# ProDoc_hapTGP_2025-10-23.net
KiCad netlist of a schematic drawn in EasyEDA Pro
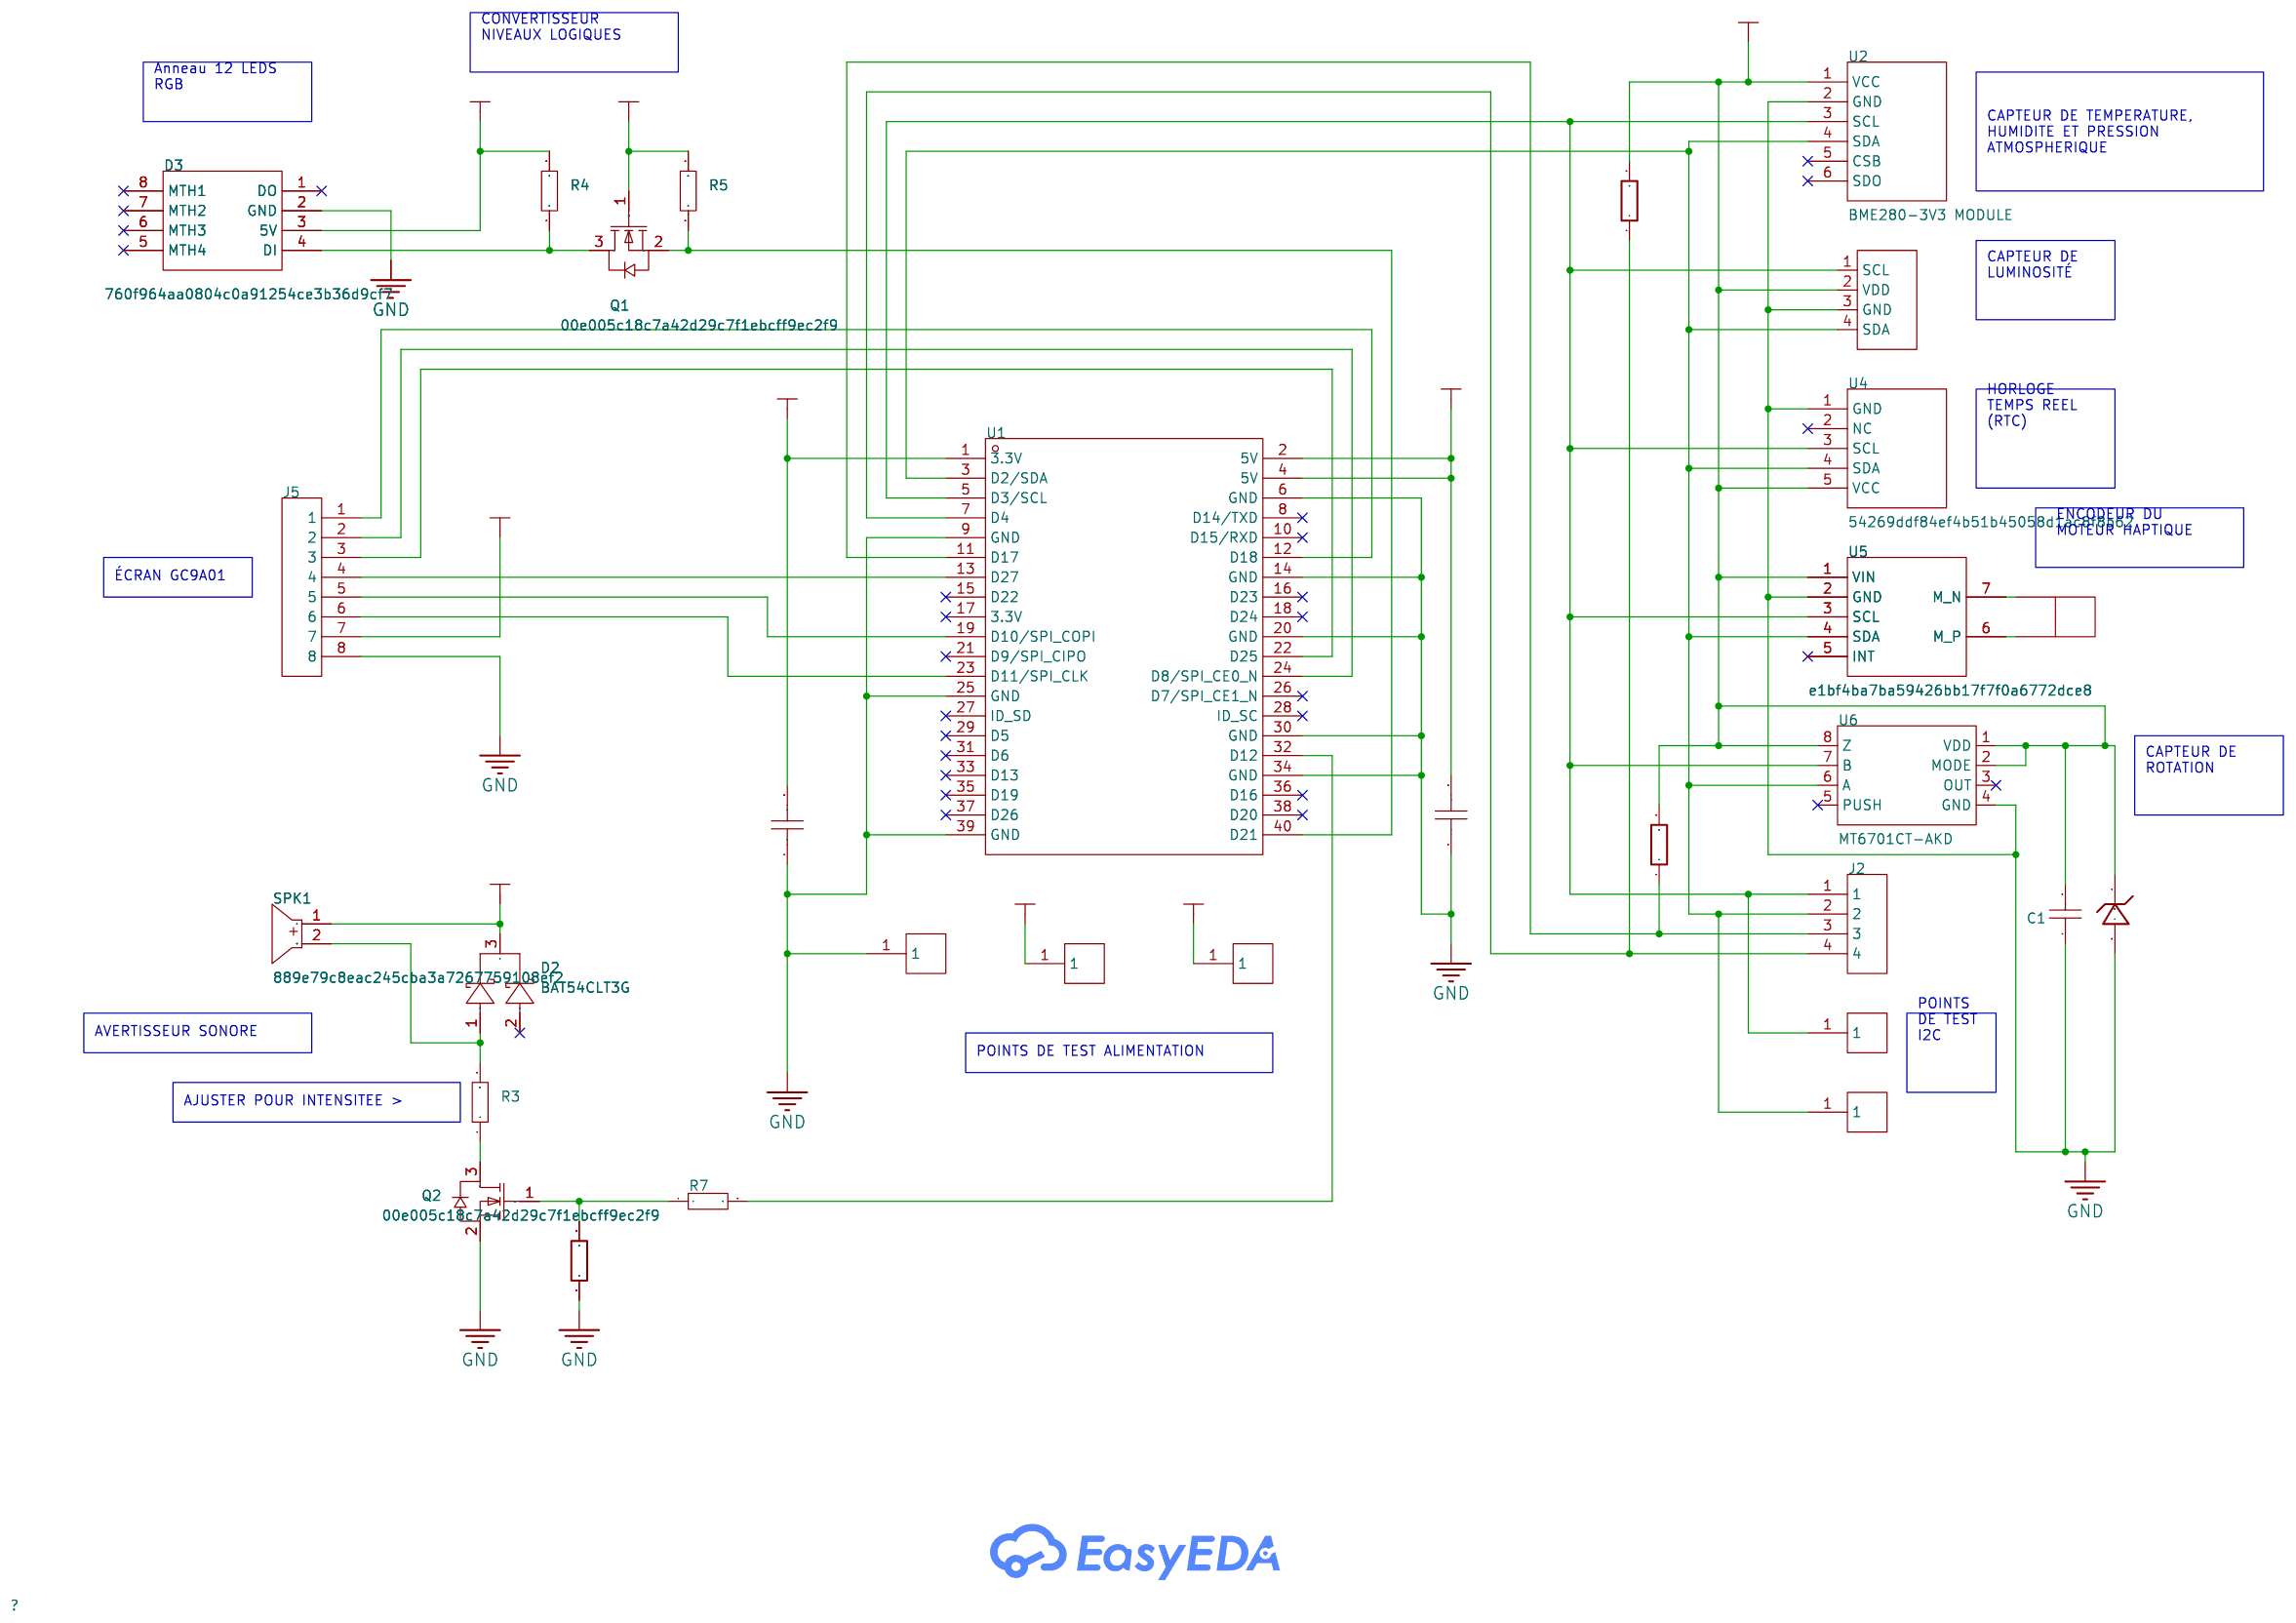
[diagram p0: P1]
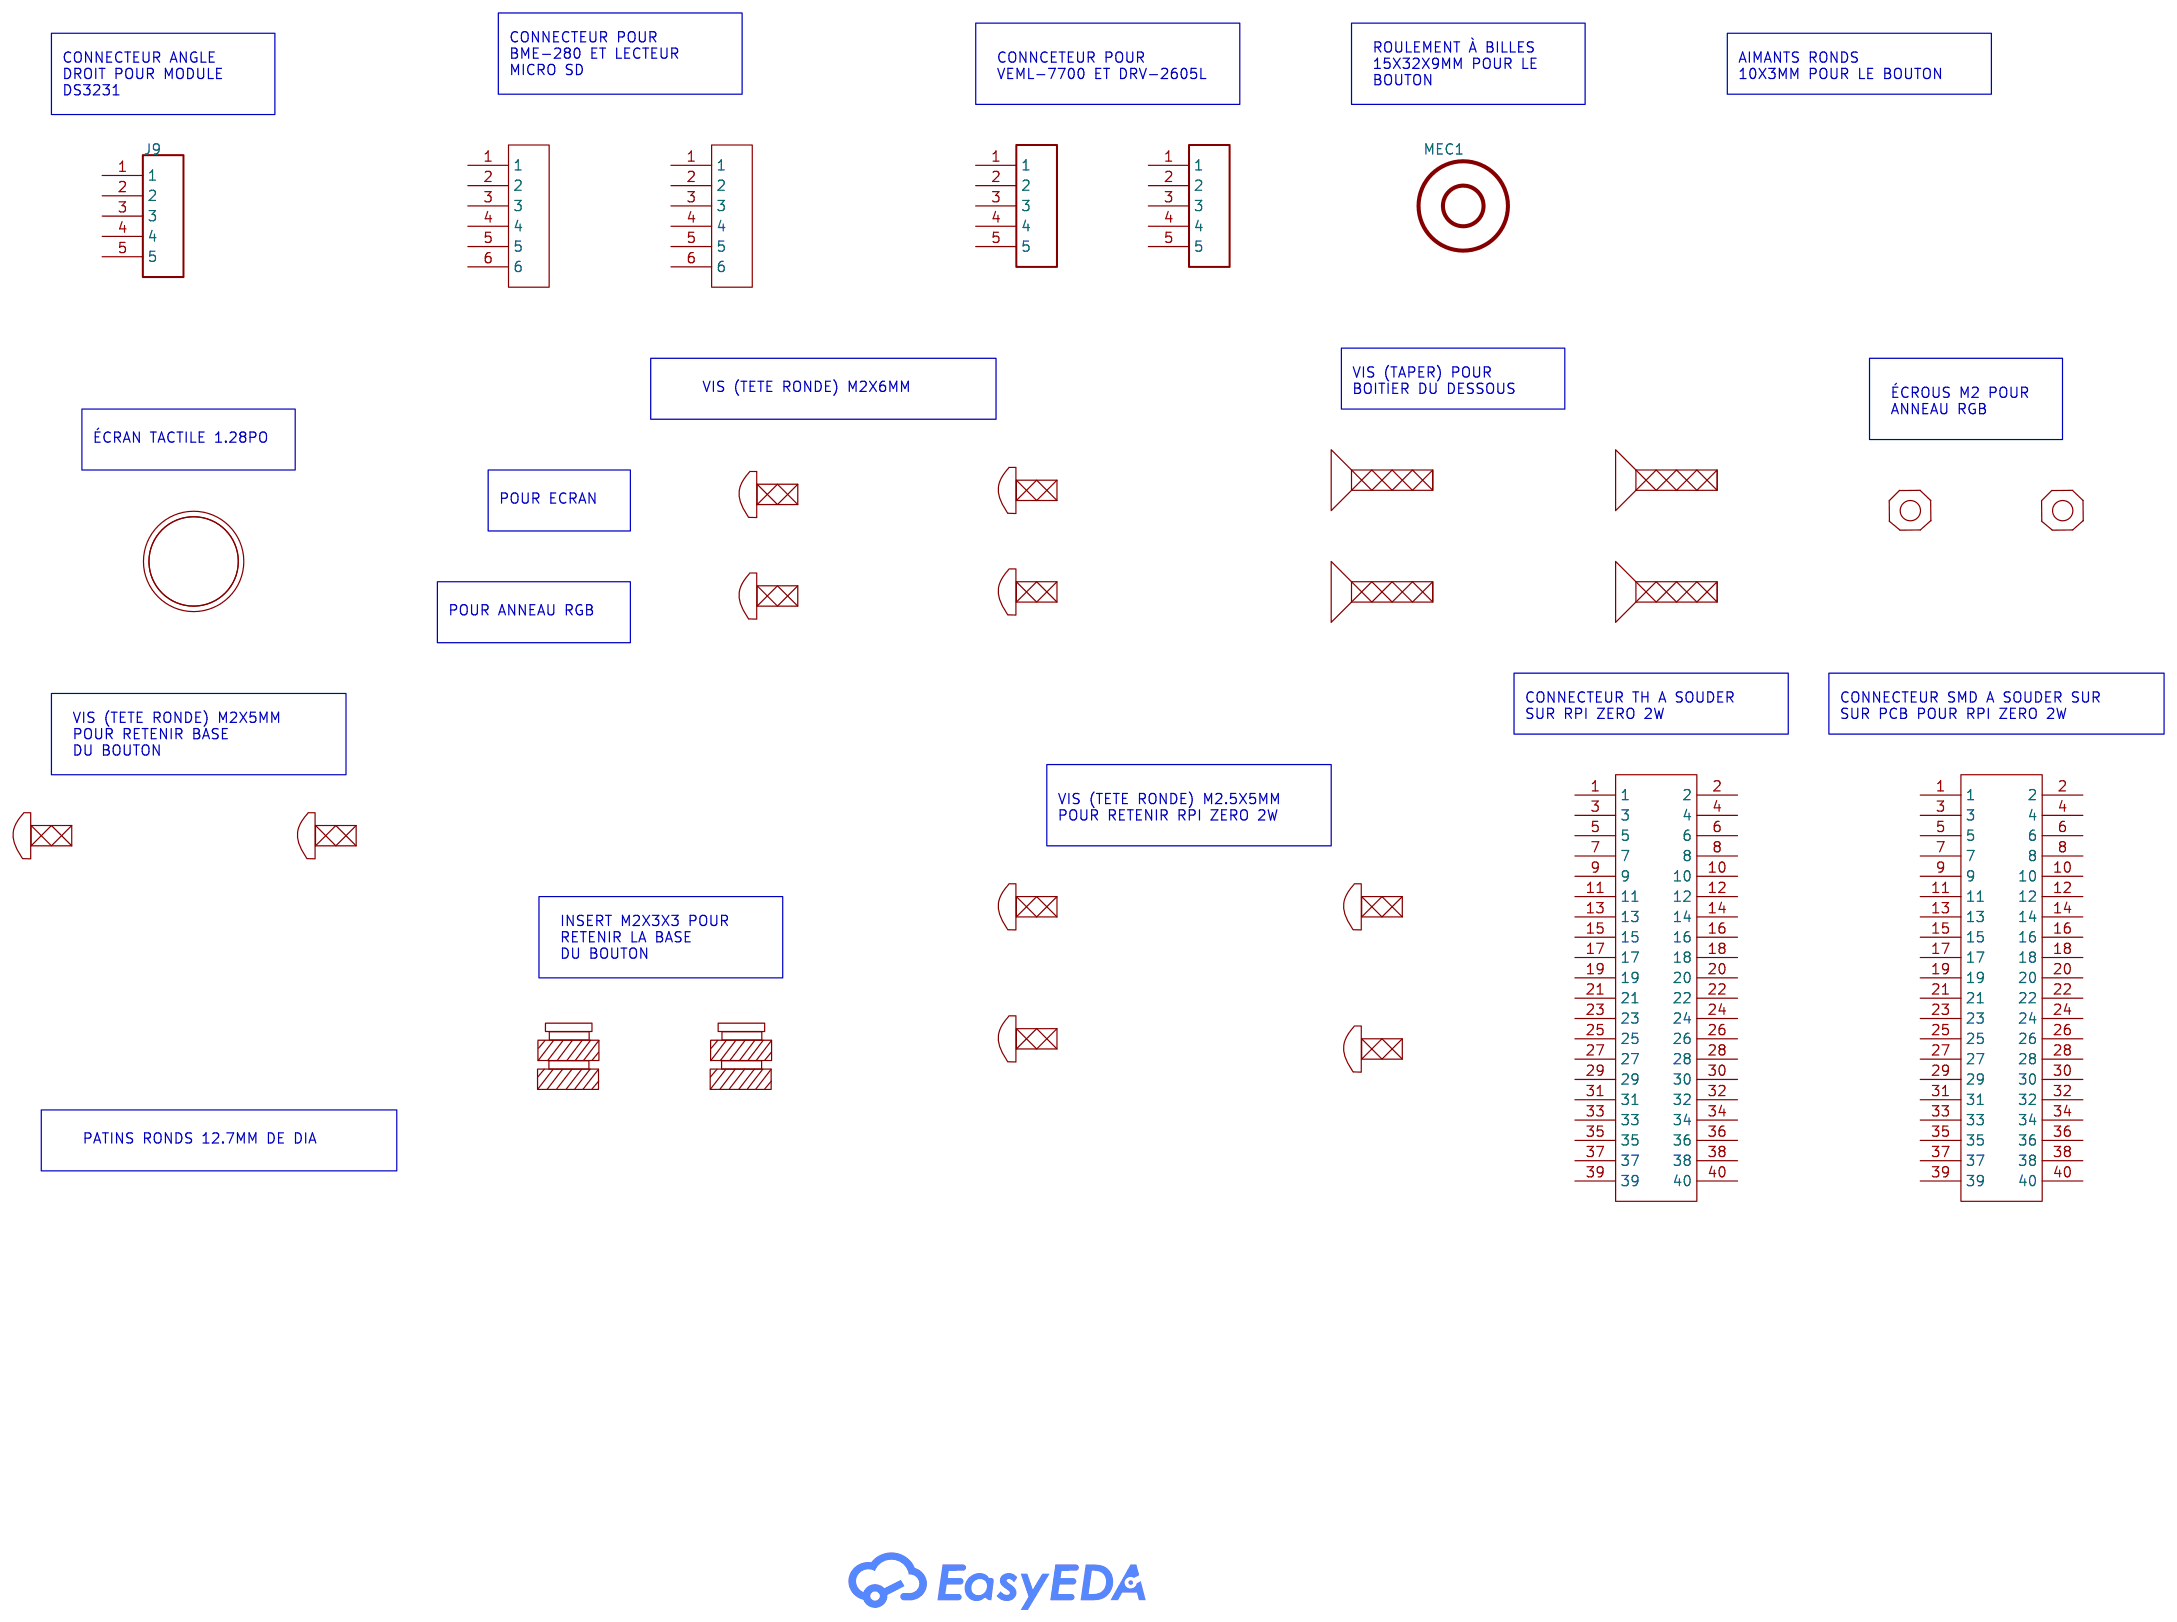
[diagram p1: P2]

(export (version "E")
  (design (tool "Eeschema 10.0.6"))
  (components
    (comp (ref "C1")
      (value "0.1uF")
      (footprint "easyedapro:C1206")
      (description "0.1 µF ±20% 50V Ceramic Capacitor X7R 1206 (3216 Metric)")
      (fields (field (name "Manufacturer Part") "C1206C104M5RAC7800") (field (name "Manufacturer") "KEMET"))
      (libsource (lib "easyedapro") (part "C1206C104M5RAC7800"))
    )
    (comp (ref "C2")
      (value "10µF")
      (footprint "easyedapro:C1206")
      (description "10 µF ±20% 16V Ceramic Capacitor X7R 1206 (3216 Metric)")
      (fields
        (field (name "Manufacturer Part") "CL31B106MOHNNNE")
        (field (name "Manufacturer") "Samsung Electro-Mechanics")
      )
      (libsource (lib "easyedapro") (part "CL31B106MOHNNNE"))
    )
    (comp (ref "C3")
      (value "10µF")
      (footprint "easyedapro:C1206")
      (description "10 µF ±20% 16V Ceramic Capacitor X7R 1206 (3216 Metric)")
      (fields
        (field (name "Manufacturer Part") "CL31B106MOHNNNE")
        (field (name "Manufacturer") "Samsung Electro-Mechanics")
      )
      (libsource (lib "easyedapro") (part "CL31B106MOHNNNE"))
    )
    (comp (ref "D1")
      (value "786c42ee781a49819dcb2175513ac30d")
      (footprint "easyedapro:SMA_L4.3-W2.6-LS5.2-RD")
      (description "10.3V Clamp 38.8A Ipp Tvs Diode Surface Mount DO-214AC (SMA)")
      (fields (field (name "Manufacturer Part") "SMAJ6.0A") (field (name "Manufacturer") "Littelfuse Inc."))
      (libsource (lib "easyedapro") (part "SMAJ6.0A"))
    )
    (comp (ref "D2")
      (value "BAT54CLT3G")
      (footprint "easyedapro:SOT-23-3_L2.9-W1.3-P1.90-LS2.4-BR_LONG_PAD")
      (description "Diode Array 1 Pair Common Cathode 30 V 200mA (DC) Surface Mount TO-236-3, SC-59, SOT-23-3")
      (fields (field (name "Manufacturer") "onsemi"))
      (libsource (lib "easyedapro") (part "BAT54C/SOT23"))
    )
    (comp (ref "D3")
      (value "760f964aa0804c0a91254ce3b36d9cf7")
      (footprint "easyedapro:12BIT_WS2812_RING")
      (description "12 Bit WS2812 Neopixel Ring")
      (fields
        (field (name "Manufacturer Part") "Color: 12 Bit")
        (field (name "Manufacturer") "WAVGAT Official Store")
      )
      (libsource (lib "easyedapro") (part "12BIT_WS2812_RING"))
    )
    (comp (ref "J2")
      (value "df3f6e4d750841a1978b57070b38a967")
      (footprint "easyedapro:TSW-104-07-G-S")
      (description "Connector Header Through Hole 4 position 0.100\" (2.54mm)")
      (fields (field (name "Manufacturer Part") "TSW-104-07-G-S") (field (name "Manufacturer") "Samtec"))
      (libsource (lib "easyedapro") (part "TSW-104-07-G-S"))
    )
    (comp (ref "J3")
      (value "25d9ce5fcc824b51a382671083746301")
      (footprint "easyedapro:TSW-101-07-G-S")
      (description "Connector Header Through Hole 1 position")
      (fields (field (name "Manufacturer Part") "TSW-101-07-G-S") (field (name "Manufacturer") "Samtec"))
      (libsource (lib "easyedapro") (part "TSW-101-07-G-S"))
    )
    (comp (ref "J4")
      (value "25d9ce5fcc824b51a382671083746301")
      (footprint "easyedapro:TSW-101-07-G-S")
      (description "Connector Header Through Hole 1 position")
      (fields (field (name "Manufacturer Part") "TSW-101-07-G-S") (field (name "Manufacturer") "Samtec"))
      (libsource (lib "easyedapro") (part "TSW-101-07-G-S"))
    )
    (comp (ref "J5")
      (value "db50c67101b641f09feebbd75da13b19")
      (footprint "easyedapro:TSW-108-07-G-S")
      (description "Connector Header Through Hole 8 position 0.100\" (2.54mm)")
      (fields (field (name "Manufacturer Part") "TSW-108-07-G-S") (field (name "Manufacturer") "Samtec"))
      (libsource (lib "easyedapro") (part "TSW-108-07-G-S"))
    )
    (comp (ref "J6")
      (value "25d9ce5fcc824b51a382671083746301")
      (footprint "easyedapro:TSW-101-07-G-S")
      (description "Connector Header Through Hole 1 position")
      (fields (field (name "Manufacturer Part") "TSW-101-07-G-S") (field (name "Manufacturer") "Samtec"))
      (libsource (lib "easyedapro") (part "TSW-101-07-G-S"))
    )
    (comp (ref "J7")
      (value "25d9ce5fcc824b51a382671083746301")
      (footprint "easyedapro:TSW-101-07-G-S")
      (description "Connector Header Through Hole 1 position")
      (fields (field (name "Manufacturer Part") "TSW-101-07-G-S") (field (name "Manufacturer") "Samtec"))
      (libsource (lib "easyedapro") (part "TSW-101-07-G-S"))
    )
    (comp (ref "J8")
      (value "25d9ce5fcc824b51a382671083746301")
      (footprint "easyedapro:TSW-101-07-G-S")
      (description "Connector Header Through Hole 1 position")
      (fields (field (name "Manufacturer Part") "TSW-101-07-G-S") (field (name "Manufacturer") "Samtec"))
      (libsource (lib "easyedapro") (part "TSW-101-07-G-S"))
    )
    (comp (ref "M1")
      (value "a87b66f22e6449f7bc229c794d7d3cd7")
      (description "DC Motor Vibration, ERM (Haptic) 3VDC")
      (fields
        (field (name "Manufacturer Part") "316040001")
        (field (name "Manufacturer") "Seeed Technology Co., Ltd")
      )
      (libsource (lib "easyedapro") (part "HAPTIC_MOTOR_10X2MM"))
    )
    (comp (ref "Q1")
      (value "00e005c18c7a42d29c7f1ebcff9ec2f9")
      (footprint "easyedapro:SOT-23-3_L2.9-W1.3-P1.90-LS2.4-BR_LONG_PAD")
      (description "N-Channel 50 V 170mA 350mW (Ta) Surface Mount SOT-23-3")
      (fields (field (name "Manufacturer Part") "BSS138") (field (name "Manufacturer") "OnSemi"))
      (libsource (lib "easyedapro") (part "BSS138"))
    )
    (comp (ref "Q2")
      (value "00e005c18c7a42d29c7f1ebcff9ec2f9")
      (footprint "easyedapro:SOT-23-3_L2.9-W1.3-P1.90-LS2.4-BR_LONG_PAD")
      (description "N-Channel 50 V 170mA 350mW (Ta) Surface Mount SOT-23-3")
      (fields (field (name "Manufacturer Part") "BSS138") (field (name "Manufacturer") "OnSemi"))
      (libsource (lib "easyedapro") (part "BSS138"))
    )
    (comp (ref "R1")
      (value "10kΩ")
      (footprint "easyedapro:R1206")
      (description "10 kOhms ±1% 0.25W, 1/4W Chip Resistor 1206 (3216 Metric) Automotive AEC-Q200 Thick Film")
      (fields
        (field (name "Manufacturer Part") "RMCF1206FT10K0")
        (field (name "Manufacturer") "Stackpole Electronics Inc")
      )
      (libsource (lib "easyedapro") (part "RMCF1206FT10K0"))
    )
    (comp (ref "R3")
      (value "100Ω")
      (footprint "easyedapro:R1206")
      (description "100 Ohms ±1% 0.25W, 1/4W Chip Resistor 1206 (3216 Metric) Automotive AEC-Q200 Thick Film")
      (fields
        (field (name "Manufacturer Part") "RMCF1206FG100R")
        (field (name "Manufacturer") "Stackpole Electronics Inc")
      )
      (libsource (lib "easyedapro") (part "RMCF1206FG100R"))
    )
    (comp (ref "R4")
      (value "1kΩ")
      (footprint "easyedapro:R1206")
      (description "1 kOhms ±1% 0.5W, 1/2W Chip Resistor 1206 (3216 Metric) Anti-Sulfur Thin Film")
      (fields
        (field (name "Manufacturer Part") "RNCP1206FTD1K00")
        (field (name "Manufacturer") "Stackpole Electronics Inc")
      )
      (libsource (lib "easyedapro") (part "RNCP1206FTD1K00"))
    )
    (comp (ref "R5")
      (value "1kΩ")
      (footprint "easyedapro:R1206")
      (description "1 kOhms ±1% 0.5W, 1/2W Chip Resistor 1206 (3216 Metric) Anti-Sulfur Thin Film")
      (fields
        (field (name "Manufacturer Part") "RNCP1206FTD1K00")
        (field (name "Manufacturer") "Stackpole Electronics Inc")
      )
      (libsource (lib "easyedapro") (part "RNCP1206FTD1K00"))
    )
    (comp (ref "R6")
      (value "10kΩ")
      (footprint "easyedapro:R1206")
      (description "10 kOhms ±1% 0.25W, 1/4W Chip Resistor 1206 (3216 Metric) Automotive AEC-Q200 Thick Film")
      (fields
        (field (name "Manufacturer Part") "RMCF1206FT10K0")
        (field (name "Manufacturer") "Stackpole Electronics Inc")
      )
      (libsource (lib "easyedapro") (part "RMCF1206FT10K0"))
    )
    (comp (ref "R7")
      (value "22.1Ω")
      (footprint "easyedapro:R1206")
      (description "22.1 Ohms ±1% 0.5W, 1/2W Chip Resistor 1206 (3216 Metric) Anti-Sulfur Thin Film")
      (fields
        (field (name "Manufacturer Part") "RNCP1206FTD22R1")
        (field (name "Manufacturer") "Stackpole Electronics Inc")
      )
      (libsource (lib "easyedapro") (part "RNCP1206FTD22R1"))
    )
    (comp (ref "R8")
      (value "3.32kΩ")
      (footprint "easyedapro:R1206")
      (description "3.32 kOhms ±1% 0.25W, 1/4W Chip Resistor 1206 (3216 Metric) Automotive AEC-Q200 Thick Film")
      (fields
        (field (name "Manufacturer Part") "RMCF1206FT3K32")
        (field (name "Manufacturer") "Stackpole Electronics Inc")
      )
      (libsource (lib "easyedapro") (part "RMCF1206FT3K32"))
    )
    (comp (ref "SPK1")
      (value "2.048kHz")
      (footprint "easyedapro:CEM-1203(42)")
      (fields (field (name "Manufacturer Part") "CEM-1203(42)") (field (name "Manufacturer") "CUI"))
      (libsource (lib "easyedapro") (part "CEM-1203(42)"))
    )
    (comp (ref "U1")
      (value "82908ec7757f43da87b5bf82fbb97953")
      (footprint "easyedapro:RPI_ZERO_2W_SMD")
      (fields (field (name "Manufacturer Part") "SC1176") (field (name "Manufacturer") "Raspberry Pi"))
      (libsource (lib "easyedapro") (part "RPI_ZERO_2W_SMD"))
    )
    (comp (ref "U2")
      (value "BME280-3V3 MODULE")
      (footprint "easyedapro:BME280-3V3")
      (description "Humidity, Pressure, Temperature 0 ~ 100% RH I2C, SPI ±3% 1 s Surface Mount")
      (fields
        (field (name "Manufacturer Part") "GY-BME280-3.3V")
        (field (name "Manufacturer") "Simple Robot Store")
      )
      (libsource (lib "easyedapro") (part "BME280-3V3 MODULE"))
    )
    (comp (ref "U4")
      (value "54269ddf84ef4b51b45058d1ac8f8b62")
      (footprint "easyedapro:DS3231_FOR_PI")
      (description "Real Time Clock (RTC) IC Clock/Calendar I2C, 2-Wire Serial")
      (fields (field (name "Manufacturer Part") "DS3231") (field (name "Manufacturer") "Simple Robot Store"))
      (libsource (lib "easyedapro") (part "DS3231_FOR_PI"))
    )
    (comp (ref "U5")
      (value "e1bf4ba7ba59426bb17f7f0a6772dce8")
      (footprint "easyedapro:DRV2605L_MODULE")
      (description "Adafruit DRV2605L Haptic Motor Controller")
      (fields
        (field (name "Manufacturer Part") "Color: Driving module")
        (field (name "Manufacturer") "Simple Robot Store")
      )
      (libsource (lib "easyedapro") (part "DRV2605L_MODULE"))
    )
    (comp (ref "U6")
      (value "MT6701CT-AKD")
      (footprint "easyedapro:SOIC-8_MT6701_LONG_PAD")
      (description "Hall Based Angle Position Encoder Sensor")
      (fields
        (field (name "Manufacturer Part") "SOP8-IIC Default")
        (field (name "Manufacturer") "Red Yellow Store")
      )
      (libsource (lib "easyedapro") (part "MT6701CT-AKD"))
    )
    (comp (ref "U7")
      (value "e600161ae6e94e2281b32d82396dab58")
      (footprint "easyedapro:VEML7700-TT")
      (description "Optical Sensor Ambient I2C 4-SMD, J-Lead - Top View")
      (fields (field (name "Manufacturer Part") "VEML7700-TT") (field (name "Manufacturer") "Vishay"))
      (libsource (lib "easyedapro") (part "VEML7700-TT"))
    )
    (comp (ref "J9")
      (value "d4bc78de218c43d6890ff5c2e1751f38")
      (footprint "easyedapro:TSW-105-08-G-S-RA")
      (description "Connector Header Through Hole, Right Angle 5 position 0.100\" (2.54mm)")
      (fields (field (name "Manufacturer Part") "TSW-105-08-G-S-RA") (field (name "Manufacturer") "Samtec"))
      (libsource (lib "easyedapro") (part "TSW-105-08-G-S-RA"))
    )
    (comp (ref "J10")
      (value "842bb1afb25c4c82b2ce2c1a00fc9b49")
      (footprint "easyedapro:TSW-106-07-G-S")
      (description "Connector Header Through Hole 6 position 0.100\" (2.54mm)")
      (fields (field (name "Manufacturer Part") "TSW-106-07-G-S") (field (name "Manufacturer") "Samtec"))
      (libsource (lib "easyedapro") (part "TSW-106-07-G-S"))
    )
    (comp (ref "J11")
      (value "842bb1afb25c4c82b2ce2c1a00fc9b49")
      (footprint "easyedapro:TSW-106-07-G-S")
      (description "Connector Header Through Hole 6 position 0.100\" (2.54mm)")
      (fields (field (name "Manufacturer Part") "TSW-106-07-G-S") (field (name "Manufacturer") "Samtec"))
      (libsource (lib "easyedapro") (part "TSW-106-07-G-S"))
    )
    (comp (ref "J12")
      (value "519a3672ea174b5fbedaf20516a41a10")
      (footprint "easyedapro:TSW-105-07-G-S")
      (description "Connector Header Through Hole 5 position 0.100\" (2.54mm)")
      (fields (field (name "Manufacturer Part") "TSW-105-07-G-S") (field (name "Manufacturer") "Samtec"))
      (libsource (lib "easyedapro") (part "TSW-105-07-G-S"))
    )
    (comp (ref "J13")
      (value "519a3672ea174b5fbedaf20516a41a10")
      (footprint "easyedapro:TSW-105-07-G-S")
      (description "Connector Header Through Hole 5 position 0.100\" (2.54mm)")
      (fields (field (name "Manufacturer Part") "TSW-105-07-G-S") (field (name "Manufacturer") "Samtec"))
      (libsource (lib "easyedapro") (part "TSW-105-07-G-S"))
    )
    (comp (ref "J14")
      (value "320c196bd822489ebe2c8557b4e2ea87")
      (footprint "easyedapro:TSW-120-07-G-D")
      (description "Connector Header Through Hole 40 position 0.100\" (2.54mm)")
      (fields (field (name "Manufacturer Part") "TSW-120-07-G-D") (field (name "Manufacturer") "Samtec"))
      (libsource (lib "easyedapro") (part "TSW-120-07-G-D"))
    )
    (comp (ref "J15")
      (value "60a980731c99412ab857ed917eeb6bae")
      (footprint "easyedapro:SSM-120-L-DV")
      (description "40 Position Receptacle, Pass Through Connector 0.100\" (2.54mm) Surface Mount Gold")
      (fields (field (name "Manufacturer Part") "SSM-120-L-DV") (field (name "Manufacturer") "Samtec"))
      (libsource (lib "easyedapro") (part "SSM-120-L-DV"))
    )
    (comp (ref "MEC1")
      (value "4874c76d77fe4fedaef2837b43ac3319")
      (fields
        (field (name "Manufacturer Part") "6002-2RS")
        (field (name "Manufacturer") "Bearing World Store")
      )
      (libsource (lib "easyedapro") (part "BEARING_15x32x9MM"))
    )
    (comp (ref "MEC2")
      (value "a5e0b033ab874c949acdb6fa7986dbbc")
      (fields
        (field (name "Manufacturer Part") "Color: 10x3mm-10PCS")
        (field (name "Manufacturer") "Magical Magnet Life Store")
      )
      (libsource (lib "easyedapro") (part "MAGNET_10X3MM_ROUND"))
    )
    (comp (ref "MEC3")
      (value "a5e0b033ab874c949acdb6fa7986dbbc")
      (fields
        (field (name "Manufacturer Part") "Color: 10x3mm-10PCS")
        (field (name "Manufacturer") "Magical Magnet Life Store")
      )
      (libsource (lib "easyedapro") (part "MAGNET_10X3MM_ROUND"))
    )
    (comp (ref "MEC4")
      (value "55b254a44b8a4a90b11fe05f35b53fb9")
      (description "1.28 inch TFT Screen Display Module 1.28\" IPS Round Colorful LCD Board GC9A01 Touch 240x240 SPI")
      (fields
        (field (name "Manufacturer Part") "Color: Module With Touch")
        (field (name "Manufacturer") "Your Cee")
      )
      (libsource (lib "easyedapro") (part "1.28IN_TFT_TOUCH_SCREEN"))
    )
    (comp (ref "MEC5")
      (value "84bc130494194e13a6b8797a8c02c4b9")
      (description "M2 Stainless steel iron plating round head, Phillips screw bolt length 6mm")
      (fields
        (field (name "Manufacturer Part") "Size: M2, Length: 6mm")
        (field (name "Manufacturer") "Darzoom Store")
      )
      (libsource (lib "easyedapro") (part "M2x6_ROUND_HEAD_SCREW"))
    )
    (comp (ref "MEC6")
      (value "84bc130494194e13a6b8797a8c02c4b9")
      (description "M2 Stainless steel iron plating round head, Phillips screw bolt length 6mm")
      (fields
        (field (name "Manufacturer Part") "Size: M2, Length: 6mm")
        (field (name "Manufacturer") "Darzoom Store")
      )
      (libsource (lib "easyedapro") (part "M2x6_ROUND_HEAD_SCREW"))
    )
    (comp (ref "MEC7")
      (value "84bc130494194e13a6b8797a8c02c4b9")
      (description "M2 Stainless steel iron plating round head, Phillips screw bolt length 6mm")
      (fields
        (field (name "Manufacturer Part") "Size: M2, Length: 6mm")
        (field (name "Manufacturer") "Darzoom Store")
      )
      (libsource (lib "easyedapro") (part "M2x6_ROUND_HEAD_SCREW"))
    )
    (comp (ref "MEC8")
      (value "84bc130494194e13a6b8797a8c02c4b9")
      (description "M2 Stainless steel iron plating round head, Phillips screw bolt length 6mm")
      (fields
        (field (name "Manufacturer Part") "Size: M2, Length: 6mm")
        (field (name "Manufacturer") "Darzoom Store")
      )
      (libsource (lib "easyedapro") (part "M2x6_ROUND_HEAD_SCREW"))
    )
    (comp (ref "MEC9")
      (value "e747b9e705f54f58a9aa79ca04ba0c74")
      (description "M3x20mm Flat Head Machine Screws")
      (fields (field (name "Manufacturer Part") "M3x20mm") (field (name "Manufacturer") "UXCELL"))
      (libsource (lib "easyedapro") (part "M3x20_FLAT_HEAD_SCREW"))
    )
    (comp (ref "MEC10")
      (value "e747b9e705f54f58a9aa79ca04ba0c74")
      (description "M3x20mm Flat Head Machine Screws")
      (fields (field (name "Manufacturer Part") "M3x20mm") (field (name "Manufacturer") "UXCELL"))
      (libsource (lib "easyedapro") (part "M3x20_FLAT_HEAD_SCREW"))
    )
    (comp (ref "MEC11")
      (value "e747b9e705f54f58a9aa79ca04ba0c74")
      (description "M3x20mm Flat Head Machine Screws")
      (fields (field (name "Manufacturer Part") "M3x20mm") (field (name "Manufacturer") "UXCELL"))
      (libsource (lib "easyedapro") (part "M3x20_FLAT_HEAD_SCREW"))
    )
    (comp (ref "MEC12")
      (value "e747b9e705f54f58a9aa79ca04ba0c74")
      (description "M3x20mm Flat Head Machine Screws")
      (fields (field (name "Manufacturer Part") "M3x20mm") (field (name "Manufacturer") "UXCELL"))
      (libsource (lib "easyedapro") (part "M3x20_FLAT_HEAD_SCREW"))
    )
    (comp (ref "MEC13")
      (value "0744fd2aaf9640809141f7db8254e100")
      (description "M2 Stainless steel iron plating round head, Phillips screw bolt length 5mm")
      (fields
        (field (name "Manufacturer Part") "Size: M2, Length: 5mm")
        (field (name "Manufacturer") "Darzoom Store")
      )
      (libsource (lib "easyedapro") (part "M2x5_ROUND_HEAD_SCREW"))
    )
    (comp (ref "MEC14")
      (value "0744fd2aaf9640809141f7db8254e100")
      (description "M2 Stainless steel iron plating round head, Phillips screw bolt length 5mm")
      (fields
        (field (name "Manufacturer Part") "Size: M2, Length: 5mm")
        (field (name "Manufacturer") "Darzoom Store")
      )
      (libsource (lib "easyedapro") (part "M2x5_ROUND_HEAD_SCREW"))
    )
    (comp (ref "MEC15")
      (value "44b7d81d582e44f3a2eef445dd88f108")
      (description "M2.5 Stainless steel iron plating round head, Phillips screw bolt length 5mm")
      (fields
        (field (name "Manufacturer Part") "Size: M2.5, Length: 5mm")
        (field (name "Manufacturer") "Darzoom Store")
      )
      (libsource (lib "easyedapro") (part "M2.5x5_ROUND_HEAD_SCREW"))
    )
    (comp (ref "MEC16")
      (value "44b7d81d582e44f3a2eef445dd88f108")
      (description "M2.5 Stainless steel iron plating round head, Phillips screw bolt length 5mm")
      (fields
        (field (name "Manufacturer Part") "Size: M2.5, Length: 5mm")
        (field (name "Manufacturer") "Darzoom Store")
      )
      (libsource (lib "easyedapro") (part "M2.5x5_ROUND_HEAD_SCREW"))
    )
    (comp (ref "MEC17")
      (value "44b7d81d582e44f3a2eef445dd88f108")
      (description "M2.5 Stainless steel iron plating round head, Phillips screw bolt length 5mm")
      (fields
        (field (name "Manufacturer Part") "Size: M2.5, Length: 5mm")
        (field (name "Manufacturer") "Darzoom Store")
      )
      (libsource (lib "easyedapro") (part "M2.5x5_ROUND_HEAD_SCREW"))
    )
    (comp (ref "MEC18")
      (value "44b7d81d582e44f3a2eef445dd88f108")
      (description "M2.5 Stainless steel iron plating round head, Phillips screw bolt length 5mm")
      (fields
        (field (name "Manufacturer Part") "Size: M2.5, Length: 5mm")
        (field (name "Manufacturer") "Darzoom Store")
      )
      (libsource (lib "easyedapro") (part "M2.5x5_ROUND_HEAD_SCREW"))
    )
    (comp (ref "MEC19")
      (value "fea318fc1c2846968e82746a332974ab")
      (description "Stainless steel iron Hex Hexagon Nut for M2 Srew Bolt")
      (fields
        (field (name "Manufacturer Part") "Size: M2 ( 50 pcs)")
        (field (name "Manufacturer") "Darzoom Store")
      )
      (libsource (lib "easyedapro") (part "M2_HEX_NUT"))
    )
    (comp (ref "MEC20")
      (value "fea318fc1c2846968e82746a332974ab")
      (description "Stainless steel iron Hex Hexagon Nut for M2 Srew Bolt")
      (fields
        (field (name "Manufacturer Part") "Size: M2 ( 50 pcs)")
        (field (name "Manufacturer") "Darzoom Store")
      )
      (libsource (lib "easyedapro") (part "M2_HEX_NUT"))
    )
    (comp (ref "MEC21")
      (value "b4d0d6735a904df985b20de909715984")
      (description "M2 Heat Set Insert for 3D Printing Components and Plastic Parts - Brass Metric Knurled Nuts")
      (fields
        (field (name "Manufacturer Part") "Colour Name: M2 X D3 X L3(100pcs)")
        (field (name "Manufacturer") "Hanglife")
      )
      (libsource (lib "easyedapro") (part "INSERT_M2X3X3"))
    )
    (comp (ref "MEC22")
      (value "b4d0d6735a904df985b20de909715984")
      (description "M2 Heat Set Insert for 3D Printing Components and Plastic Parts - Brass Metric Knurled Nuts")
      (fields
        (field (name "Manufacturer Part") "Colour Name: M2 X D3 X L3(100pcs)")
        (field (name "Manufacturer") "Hanglife")
      )
      (libsource (lib "easyedapro") (part "INSERT_M2X3X3"))
    )
    (comp (ref "MEC23")
      (value "3b06449f621e43b7b0359324f8e45c47")
      (description "Round 12.7mm Cabinet Bumpers Soft Self-Adhesive Clear Rubber Bumper")
      (fields
        (field (name "Manufacturer Part") "Size: Cylindrical 96pcs")
        (field (name "Manufacturer") "Furnigear")
      )
      (libsource (lib "easyedapro") (part "ClearRubberBumper_12.7MM"))
    )
    (comp (ref "MEC24")
      (value "3b06449f621e43b7b0359324f8e45c47")
      (description "Round 12.7mm Cabinet Bumpers Soft Self-Adhesive Clear Rubber Bumper")
      (fields
        (field (name "Manufacturer Part") "Size: Cylindrical 96pcs")
        (field (name "Manufacturer") "Furnigear")
      )
      (libsource (lib "easyedapro") (part "ClearRubberBumper_12.7MM"))
    )
    (comp (ref "MEC25")
      (value "3b06449f621e43b7b0359324f8e45c47")
      (description "Round 12.7mm Cabinet Bumpers Soft Self-Adhesive Clear Rubber Bumper")
      (fields
        (field (name "Manufacturer Part") "Size: Cylindrical 96pcs")
        (field (name "Manufacturer") "Furnigear")
      )
      (libsource (lib "easyedapro") (part "ClearRubberBumper_12.7MM"))
    )
    (comp (ref "MEC26")
      (value "3b06449f621e43b7b0359324f8e45c47")
      (description "Round 12.7mm Cabinet Bumpers Soft Self-Adhesive Clear Rubber Bumper")
      (fields
        (field (name "Manufacturer Part") "Size: Cylindrical 96pcs")
        (field (name "Manufacturer") "Furnigear")
      )
      (libsource (lib "easyedapro") (part "ClearRubberBumper_12.7MM"))
    )
  )
  (nets
    (net (code "1") (name "3V3") (class "Default")
      (node (ref "C1") (pin "2") (pinfunction "2_2") (pintype "input"))
      (node (ref "C3") (pin "2") (pinfunction "2_2") (pintype "unspecified"))
      (node (ref "D1") (pin "1") (pinfunction "C_1") (pintype "unspecified"))
      (node (ref "D2") (pin "3") (pinfunction "K_3") (pintype "unspecified"))
      (node (ref "J5") (pin "7") (pinfunction "7_7") (pintype "input"))
      (node (ref "J8") (pin "1") (pinfunction "1_1") (pintype "unspecified"))
      (node (ref "Q1") (pin "1") (pinfunction "G_1") (pintype "unspecified"))
      (node (ref "R1") (pin "2") (pinfunction "2_2") (pintype "unspecified"))
      (node (ref "R5") (pin "2") (pinfunction "2_2") (pintype "unspecified"))
      (node (ref "R8") (pin "2") (pinfunction "2_2") (pintype "unspecified"))
      (node (ref "SPK1") (pin "1") (pinfunction "1_1") (pintype "unspecified"))
      (node (ref "U1") (pin "1") (pinfunction "3.3V_1") (pintype "unspecified"))
      (node (ref "U2") (pin "1") (pinfunction "VCC_1") (pintype "unspecified"))
      (node (ref "U4") (pin "5") (pinfunction "VCC_5") (pintype "unspecified"))
      (node (ref "U5") (pin "1") (pinfunction "VIN_1") (pintype "input"))
      (node (ref "U6") (pin "1") (pinfunction "VDD_1") (pintype "unspecified"))
      (node (ref "U6") (pin "2") (pinfunction "MODE_2") (pintype "unspecified"))
      (node (ref "U6") (pin "8") (pinfunction "Z_8") (pintype "unspecified"))
      (node (ref "U7") (pin "2") (pinfunction "VDD_2") (pintype "unspecified"))
    )
    (net (code "2") (name "5V0") (class "Default")
      (node (ref "C2") (pin "2") (pinfunction "2_2") (pintype "unspecified"))
      (node (ref "D3") (pin "3") (pinfunction "5V_3") (pintype "input"))
      (node (ref "J7") (pin "1") (pinfunction "1_1") (pintype "unspecified"))
      (node (ref "R4") (pin "2") (pinfunction "2_2") (pintype "unspecified"))
      (node (ref "U1") (pin "2") (pinfunction "5V_2") (pintype "unspecified"))
      (node (ref "U1") (pin "4") (pinfunction "5V_4") (pintype "unspecified"))
    )
    (net (code "3") (name "GND") (class "Default")
      (node (ref "C1") (pin "1") (pinfunction "1_1") (pintype "input"))
      (node (ref "C2") (pin "1") (pinfunction "1_1") (pintype "unspecified"))
      (node (ref "C3") (pin "1") (pinfunction "1_1") (pintype "unspecified"))
      (node (ref "D1") (pin "2") (pinfunction "A_2") (pintype "unspecified"))
      (node (ref "D3") (pin "2") (pinfunction "GND_2") (pintype "input"))
      (node (ref "J5") (pin "8") (pinfunction "8_8") (pintype "input"))
      (node (ref "J6") (pin "1") (pinfunction "1_1") (pintype "unspecified"))
      (node (ref "Q2") (pin "2") (pinfunction "S_2") (pintype "unspecified"))
      (node (ref "R6") (pin "1") (pinfunction "1_1") (pintype "unspecified"))
      (node (ref "U1") (pin "14") (pinfunction "GND_14") (pintype "unspecified"))
      (node (ref "U1") (pin "20") (pinfunction "GND_20") (pintype "unspecified"))
      (node (ref "U1") (pin "25") (pinfunction "GND_25") (pintype "unspecified"))
      (node (ref "U1") (pin "30") (pinfunction "GND_30") (pintype "unspecified"))
      (node (ref "U1") (pin "34") (pinfunction "GND_34") (pintype "unspecified"))
      (node (ref "U1") (pin "39") (pinfunction "GND_39") (pintype "unspecified"))
      (node (ref "U1") (pin "6") (pinfunction "GND_6") (pintype "unspecified"))
      (node (ref "U1") (pin "9") (pinfunction "GND_9") (pintype "unspecified"))
      (node (ref "U2") (pin "2") (pinfunction "GND_2") (pintype "unspecified"))
      (node (ref "U4") (pin "1") (pinfunction "GND_1") (pintype "unspecified"))
      (node (ref "U5") (pin "2") (pinfunction "GND_2") (pintype "input"))
      (node (ref "U6") (pin "4") (pinfunction "GND_4") (pintype "unspecified"))
      (node (ref "U7") (pin "3") (pinfunction "GND_3") (pintype "unspecified"))
    )
    (net (code "4") (name "Net-(D2-A-Pad1)") (class "Default")
      (node (ref "D2") (pin "1") (pinfunction "A_1") (pintype "unspecified"))
      (node (ref "R3") (pin "2") (pinfunction "2_2") (pintype "unspecified"))
      (node (ref "SPK1") (pin "2") (pinfunction "2_2") (pintype "unspecified"))
    )
    (net (code "5") (name "Net-(D3-DI)") (class "Default")
      (node (ref "D3") (pin "4") (pinfunction "DI_4") (pintype "input"))
      (node (ref "Q1") (pin "3") (pinfunction "D_3") (pintype "unspecified"))
      (node (ref "R4") (pin "1") (pinfunction "1_1") (pintype "unspecified"))
    )
    (net (code "6") (name "Net-(Q1-S)") (class "Default")
      (node (ref "Q1") (pin "2") (pinfunction "S_2") (pintype "unspecified"))
      (node (ref "R5") (pin "1") (pinfunction "1_1") (pintype "unspecified"))
      (node (ref "U1") (pin "40") (pinfunction "D21_40") (pintype "unspecified"))
    )
    (net (code "7") (name "Net-(Q2-D)") (class "Default")
      (node (ref "Q2") (pin "3") (pinfunction "D_3") (pintype "unspecified"))
      (node (ref "R3") (pin "1") (pinfunction "1_1") (pintype "unspecified"))
    )
    (net (code "8") (name "Net-(Q2-G)") (class "Default")
      (node (ref "Q2") (pin "1") (pinfunction "G_1") (pintype "unspecified"))
      (node (ref "R6") (pin "2") (pinfunction "2_2") (pintype "unspecified"))
      (node (ref "R7") (pin "1") (pinfunction "1_1") (pintype "unspecified"))
    )
    (net (code "9") (name "Net-(U1-D2{slash}SDA)") (class "Default")
      (node (ref "J2") (pin "2") (pinfunction "2_2") (pintype "input"))
      (node (ref "J4") (pin "1") (pinfunction "1_1") (pintype "unspecified"))
      (node (ref "U1") (pin "3") (pinfunction "D2/SDA_3") (pintype "unspecified"))
      (node (ref "U2") (pin "4") (pinfunction "SDA_4") (pintype "unspecified"))
      (node (ref "U4") (pin "4") (pinfunction "SDA_4") (pintype "unspecified"))
      (node (ref "U5") (pin "4") (pinfunction "SDA_4") (pintype "input"))
      (node (ref "U6") (pin "6") (pinfunction "A_6") (pintype "unspecified"))
      (node (ref "U7") (pin "4") (pinfunction "SDA_4") (pintype "unspecified"))
    )
    (net (code "10") (name "Net-(U1-D3{slash}SCL)") (class "Default")
      (node (ref "J2") (pin "1") (pinfunction "1_1") (pintype "input"))
      (node (ref "J3") (pin "1") (pinfunction "1_1") (pintype "unspecified"))
      (node (ref "U1") (pin "5") (pinfunction "D3/SCL_5") (pintype "unspecified"))
      (node (ref "U2") (pin "3") (pinfunction "SCL_3") (pintype "unspecified"))
      (node (ref "U4") (pin "3") (pinfunction "SCL_3") (pintype "unspecified"))
      (node (ref "U5") (pin "3") (pinfunction "SCL_3") (pintype "input"))
      (node (ref "U6") (pin "7") (pinfunction "B_7") (pintype "unspecified"))
      (node (ref "U7") (pin "1") (pinfunction "SCL_1") (pintype "unspecified"))
    )
    (net (code "11") (name "Net-(U1-D4)") (class "Default")
      (node (ref "J2") (pin "4") (pinfunction "4_4") (pintype "input"))
      (node (ref "R1") (pin "1") (pinfunction "1_1") (pintype "unspecified"))
      (node (ref "U1") (pin "7") (pinfunction "D4_7") (pintype "unspecified"))
    )
    (net (code "12") (name "Net-(U1-D8{slash}SPI_CE0_N)") (class "Default")
      (node (ref "J5") (pin "2") (pinfunction "2_2") (pintype "input"))
      (node (ref "U1") (pin "24") (pinfunction "D8/SPI_CE0_N_24") (pintype "unspecified"))
    )
    (net (code "13") (name "Net-(U1-D10{slash}SPI_COPI)") (class "Default")
      (node (ref "J5") (pin "5") (pinfunction "5_5") (pintype "input"))
      (node (ref "U1") (pin "19") (pinfunction "D10/SPI_COPI_19") (pintype "unspecified"))
    )
    (net (code "14") (name "Net-(U1-D11{slash}SPI_CLK)") (class "Default")
      (node (ref "J5") (pin "6") (pinfunction "6_6") (pintype "input"))
      (node (ref "U1") (pin "23") (pinfunction "D11/SPI_CLK_23") (pintype "unspecified"))
    )
    (net (code "15") (name "Net-(U1-D12)") (class "Default")
      (node (ref "R7") (pin "2") (pinfunction "2_2") (pintype "unspecified"))
      (node (ref "U1") (pin "32") (pinfunction "D12_32") (pintype "unspecified"))
    )
    (net (code "16") (name "Net-(U1-D17)") (class "Default")
      (node (ref "J2") (pin "3") (pinfunction "3_3") (pintype "input"))
      (node (ref "R8") (pin "1") (pinfunction "1_1") (pintype "unspecified"))
      (node (ref "U1") (pin "11") (pinfunction "D17_11") (pintype "unspecified"))
    )
    (net (code "17") (name "Net-(U1-D18)") (class "Default")
      (node (ref "J5") (pin "1") (pinfunction "1_1") (pintype "input"))
      (node (ref "U1") (pin "12") (pinfunction "D18_12") (pintype "unspecified"))
    )
    (net (code "18") (name "Net-(U1-D25)") (class "Default")
      (node (ref "J5") (pin "3") (pinfunction "3_3") (pintype "input"))
      (node (ref "U1") (pin "22") (pinfunction "D25_22") (pintype "unspecified"))
    )
    (net (code "19") (name "Net-(U1-D27)") (class "Default")
      (node (ref "J5") (pin "4") (pinfunction "4_4") (pintype "input"))
      (node (ref "U1") (pin "13") (pinfunction "D27_13") (pintype "unspecified"))
    )
    (net (code "20") (name "unconnected-(D2-A-Pad2)") (class "Default")
      (node (ref "D2") (pin "2") (pinfunction "A_2") (pintype "unspecified+no_connect"))
    )
    (net (code "21") (name "unconnected-(D3-DO-Pad1)") (class "Default")
      (node (ref "D3") (pin "1") (pinfunction "DO_1") (pintype "input+no_connect"))
    )
    (net (code "22") (name "unconnected-(D3-MTH1-Pad8)") (class "Default")
      (node (ref "D3") (pin "8") (pinfunction "MTH1_8") (pintype "input+no_connect"))
    )
    (net (code "23") (name "unconnected-(D3-MTH2-Pad7)") (class "Default")
      (node (ref "D3") (pin "7") (pinfunction "MTH2_7") (pintype "input+no_connect"))
    )
    (net (code "24") (name "unconnected-(D3-MTH3-Pad6)") (class "Default")
      (node (ref "D3") (pin "6") (pinfunction "MTH3_6") (pintype "input+no_connect"))
    )
    (net (code "25") (name "unconnected-(D3-MTH4-Pad5)") (class "Default")
      (node (ref "D3") (pin "5") (pinfunction "MTH4_5") (pintype "input+no_connect"))
    )
    (net (code "26") (name "unconnected-(J9-Pad1)") (class "Default")
      (node (ref "J9") (pin "1") (pinfunction "1_1") (pintype "unspecified"))
    )
    (net (code "27") (name "unconnected-(J9-Pad2)") (class "Default")
      (node (ref "J9") (pin "2") (pinfunction "2_2") (pintype "unspecified"))
    )
    (net (code "28") (name "unconnected-(J9-Pad3)") (class "Default")
      (node (ref "J9") (pin "3") (pinfunction "3_3") (pintype "unspecified"))
    )
    (net (code "29") (name "unconnected-(J9-Pad4)") (class "Default")
      (node (ref "J9") (pin "4") (pinfunction "4_4") (pintype "unspecified"))
    )
    (net (code "30") (name "unconnected-(J9-Pad5)") (class "Default")
      (node (ref "J9") (pin "5") (pinfunction "5_5") (pintype "unspecified"))
    )
    (net (code "31") (name "unconnected-(J10-Pad1)") (class "Default")
      (node (ref "J10") (pin "1") (pinfunction "1_1") (pintype "unspecified"))
    )
    (net (code "32") (name "unconnected-(J10-Pad2)") (class "Default")
      (node (ref "J10") (pin "2") (pinfunction "2_2") (pintype "unspecified"))
    )
    (net (code "33") (name "unconnected-(J10-Pad3)") (class "Default")
      (node (ref "J10") (pin "3") (pinfunction "3_3") (pintype "unspecified"))
    )
    (net (code "34") (name "unconnected-(J10-Pad4)") (class "Default")
      (node (ref "J10") (pin "4") (pinfunction "4_4") (pintype "unspecified"))
    )
    (net (code "35") (name "unconnected-(J10-Pad5)") (class "Default")
      (node (ref "J10") (pin "5") (pinfunction "5_5") (pintype "unspecified"))
    )
    (net (code "36") (name "unconnected-(J10-Pad6)") (class "Default")
      (node (ref "J10") (pin "6") (pinfunction "6_6") (pintype "unspecified"))
    )
    (net (code "37") (name "unconnected-(J11-Pad1)") (class "Default")
      (node (ref "J11") (pin "1") (pinfunction "1_1") (pintype "unspecified"))
    )
    (net (code "38") (name "unconnected-(J11-Pad2)") (class "Default")
      (node (ref "J11") (pin "2") (pinfunction "2_2") (pintype "unspecified"))
    )
    (net (code "39") (name "unconnected-(J11-Pad3)") (class "Default")
      (node (ref "J11") (pin "3") (pinfunction "3_3") (pintype "unspecified"))
    )
    (net (code "40") (name "unconnected-(J11-Pad4)") (class "Default")
      (node (ref "J11") (pin "4") (pinfunction "4_4") (pintype "unspecified"))
    )
    (net (code "41") (name "unconnected-(J11-Pad5)") (class "Default")
      (node (ref "J11") (pin "5") (pinfunction "5_5") (pintype "unspecified"))
    )
    (net (code "42") (name "unconnected-(J11-Pad6)") (class "Default")
      (node (ref "J11") (pin "6") (pinfunction "6_6") (pintype "unspecified"))
    )
    (net (code "43") (name "unconnected-(J12-Pad1)") (class "Default")
      (node (ref "J12") (pin "1") (pinfunction "1_1") (pintype "unspecified"))
    )
    (net (code "44") (name "unconnected-(J12-Pad2)") (class "Default")
      (node (ref "J12") (pin "2") (pinfunction "2_2") (pintype "unspecified"))
    )
    (net (code "45") (name "unconnected-(J12-Pad3)") (class "Default")
      (node (ref "J12") (pin "3") (pinfunction "3_3") (pintype "unspecified"))
    )
    (net (code "46") (name "unconnected-(J12-Pad4)") (class "Default")
      (node (ref "J12") (pin "4") (pinfunction "4_4") (pintype "unspecified"))
    )
    (net (code "47") (name "unconnected-(J12-Pad5)") (class "Default")
      (node (ref "J12") (pin "5") (pinfunction "5_5") (pintype "unspecified"))
    )
    (net (code "48") (name "unconnected-(J13-Pad1)") (class "Default")
      (node (ref "J13") (pin "1") (pinfunction "1_1") (pintype "unspecified"))
    )
    (net (code "49") (name "unconnected-(J13-Pad2)") (class "Default")
      (node (ref "J13") (pin "2") (pinfunction "2_2") (pintype "unspecified"))
    )
    (net (code "50") (name "unconnected-(J13-Pad3)") (class "Default")
      (node (ref "J13") (pin "3") (pinfunction "3_3") (pintype "unspecified"))
    )
    (net (code "51") (name "unconnected-(J13-Pad4)") (class "Default")
      (node (ref "J13") (pin "4") (pinfunction "4_4") (pintype "unspecified"))
    )
    (net (code "52") (name "unconnected-(J13-Pad5)") (class "Default")
      (node (ref "J13") (pin "5") (pinfunction "5_5") (pintype "unspecified"))
    )
    (net (code "53") (name "unconnected-(J14-Pad1)") (class "Default")
      (node (ref "J14") (pin "1") (pinfunction "1_1") (pintype "input"))
    )
    (net (code "54") (name "unconnected-(J14-Pad2)") (class "Default")
      (node (ref "J14") (pin "2") (pinfunction "2_2") (pintype "input"))
    )
    (net (code "55") (name "unconnected-(J14-Pad3)") (class "Default")
      (node (ref "J14") (pin "3") (pinfunction "3_3") (pintype "input"))
    )
    (net (code "56") (name "unconnected-(J14-Pad4)") (class "Default")
      (node (ref "J14") (pin "4") (pinfunction "4_4") (pintype "input"))
    )
    (net (code "57") (name "unconnected-(J14-Pad5)") (class "Default")
      (node (ref "J14") (pin "5") (pinfunction "5_5") (pintype "input"))
    )
    (net (code "58") (name "unconnected-(J14-Pad6)") (class "Default")
      (node (ref "J14") (pin "6") (pinfunction "6_6") (pintype "input"))
    )
    (net (code "59") (name "unconnected-(J14-Pad7)") (class "Default")
      (node (ref "J14") (pin "7") (pinfunction "7_7") (pintype "input"))
    )
    (net (code "60") (name "unconnected-(J14-Pad8)") (class "Default")
      (node (ref "J14") (pin "8") (pinfunction "8_8") (pintype "input"))
    )
    (net (code "61") (name "unconnected-(J14-Pad9)") (class "Default")
      (node (ref "J14") (pin "9") (pinfunction "9_9") (pintype "input"))
    )
    (net (code "62") (name "unconnected-(J14-Pad10)") (class "Default")
      (node (ref "J14") (pin "10") (pinfunction "10_10") (pintype "input"))
    )
    (net (code "63") (name "unconnected-(J14-Pad11)") (class "Default")
      (node (ref "J14") (pin "11") (pinfunction "11_11") (pintype "input"))
    )
    (net (code "64") (name "unconnected-(J14-Pad12)") (class "Default")
      (node (ref "J14") (pin "12") (pinfunction "12_12") (pintype "input"))
    )
    (net (code "65") (name "unconnected-(J14-Pad13)") (class "Default")
      (node (ref "J14") (pin "13") (pinfunction "13_13") (pintype "input"))
    )
    (net (code "66") (name "unconnected-(J14-Pad14)") (class "Default")
      (node (ref "J14") (pin "14") (pinfunction "14_14") (pintype "input"))
    )
    (net (code "67") (name "unconnected-(J14-Pad15)") (class "Default")
      (node (ref "J14") (pin "15") (pinfunction "15_15") (pintype "input"))
    )
    (net (code "68") (name "unconnected-(J14-Pad16)") (class "Default")
      (node (ref "J14") (pin "16") (pinfunction "16_16") (pintype "input"))
    )
    (net (code "69") (name "unconnected-(J14-Pad17)") (class "Default")
      (node (ref "J14") (pin "17") (pinfunction "17_17") (pintype "input"))
    )
    (net (code "70") (name "unconnected-(J14-Pad18)") (class "Default")
      (node (ref "J14") (pin "18") (pinfunction "18_18") (pintype "input"))
    )
    (net (code "71") (name "unconnected-(J14-Pad19)") (class "Default")
      (node (ref "J14") (pin "19") (pinfunction "19_19") (pintype "input"))
    )
    (net (code "72") (name "unconnected-(J14-Pad20)") (class "Default")
      (node (ref "J14") (pin "20") (pinfunction "20_20") (pintype "input"))
    )
    (net (code "73") (name "unconnected-(J14-Pad21)") (class "Default")
      (node (ref "J14") (pin "21") (pinfunction "21_21") (pintype "input"))
    )
    (net (code "74") (name "unconnected-(J14-Pad22)") (class "Default")
      (node (ref "J14") (pin "22") (pinfunction "22_22") (pintype "input"))
    )
    (net (code "75") (name "unconnected-(J14-Pad23)") (class "Default")
      (node (ref "J14") (pin "23") (pinfunction "23_23") (pintype "input"))
    )
    (net (code "76") (name "unconnected-(J14-Pad24)") (class "Default")
      (node (ref "J14") (pin "24") (pinfunction "24_24") (pintype "input"))
    )
    (net (code "77") (name "unconnected-(J14-Pad25)") (class "Default")
      (node (ref "J14") (pin "25") (pinfunction "25_25") (pintype "input"))
    )
    (net (code "78") (name "unconnected-(J14-Pad26)") (class "Default")
      (node (ref "J14") (pin "26") (pinfunction "26_26") (pintype "input"))
    )
    (net (code "79") (name "unconnected-(J14-Pad27)") (class "Default")
      (node (ref "J14") (pin "27") (pinfunction "27_27") (pintype "input"))
    )
    (net (code "80") (name "unconnected-(J14-Pad28)") (class "Default")
      (node (ref "J14") (pin "28") (pinfunction "28_28") (pintype "input"))
    )
    (net (code "81") (name "unconnected-(J14-Pad29)") (class "Default")
      (node (ref "J14") (pin "29") (pinfunction "29_29") (pintype "input"))
    )
    (net (code "82") (name "unconnected-(J14-Pad30)") (class "Default")
      (node (ref "J14") (pin "30") (pinfunction "30_30") (pintype "input"))
    )
    (net (code "83") (name "unconnected-(J14-Pad31)") (class "Default")
      (node (ref "J14") (pin "31") (pinfunction "31_31") (pintype "input"))
    )
    (net (code "84") (name "unconnected-(J14-Pad32)") (class "Default")
      (node (ref "J14") (pin "32") (pinfunction "32_32") (pintype "input"))
    )
    (net (code "85") (name "unconnected-(J14-Pad33)") (class "Default")
      (node (ref "J14") (pin "33") (pinfunction "33_33") (pintype "input"))
    )
    (net (code "86") (name "unconnected-(J14-Pad34)") (class "Default")
      (node (ref "J14") (pin "34") (pinfunction "34_34") (pintype "input"))
    )
    (net (code "87") (name "unconnected-(J14-Pad35)") (class "Default")
      (node (ref "J14") (pin "35") (pinfunction "35_35") (pintype "input"))
    )
    (net (code "88") (name "unconnected-(J14-Pad36)") (class "Default")
      (node (ref "J14") (pin "36") (pinfunction "36_36") (pintype "input"))
    )
    (net (code "89") (name "unconnected-(J14-Pad37)") (class "Default")
      (node (ref "J14") (pin "37") (pinfunction "37_37") (pintype "input"))
    )
    (net (code "90") (name "unconnected-(J14-Pad38)") (class "Default")
      (node (ref "J14") (pin "38") (pinfunction "38_38") (pintype "input"))
    )
    (net (code "91") (name "unconnected-(J14-Pad39)") (class "Default")
      (node (ref "J14") (pin "39") (pinfunction "39_39") (pintype "input"))
    )
    (net (code "92") (name "unconnected-(J14-Pad40)") (class "Default")
      (node (ref "J14") (pin "40") (pinfunction "40_40") (pintype "input"))
    )
    (net (code "93") (name "unconnected-(J15-Pad1)") (class "Default")
      (node (ref "J15") (pin "1") (pinfunction "1_1") (pintype "input"))
    )
    (net (code "94") (name "unconnected-(J15-Pad2)") (class "Default")
      (node (ref "J15") (pin "2") (pinfunction "2_2") (pintype "input"))
    )
    (net (code "95") (name "unconnected-(J15-Pad3)") (class "Default")
      (node (ref "J15") (pin "3") (pinfunction "3_3") (pintype "input"))
    )
    (net (code "96") (name "unconnected-(J15-Pad4)") (class "Default")
      (node (ref "J15") (pin "4") (pinfunction "4_4") (pintype "input"))
    )
    (net (code "97") (name "unconnected-(J15-Pad5)") (class "Default")
      (node (ref "J15") (pin "5") (pinfunction "5_5") (pintype "input"))
    )
    (net (code "98") (name "unconnected-(J15-Pad6)") (class "Default")
      (node (ref "J15") (pin "6") (pinfunction "6_6") (pintype "input"))
    )
    (net (code "99") (name "unconnected-(J15-Pad7)") (class "Default")
      (node (ref "J15") (pin "7") (pinfunction "7_7") (pintype "input"))
    )
    (net (code "100") (name "unconnected-(J15-Pad8)") (class "Default")
      (node (ref "J15") (pin "8") (pinfunction "8_8") (pintype "input"))
    )
    (net (code "101") (name "unconnected-(J15-Pad9)") (class "Default")
      (node (ref "J15") (pin "9") (pinfunction "9_9") (pintype "input"))
    )
    (net (code "102") (name "unconnected-(J15-Pad10)") (class "Default")
      (node (ref "J15") (pin "10") (pinfunction "10_10") (pintype "input"))
    )
    (net (code "103") (name "unconnected-(J15-Pad11)") (class "Default")
      (node (ref "J15") (pin "11") (pinfunction "11_11") (pintype "input"))
    )
    (net (code "104") (name "unconnected-(J15-Pad12)") (class "Default")
      (node (ref "J15") (pin "12") (pinfunction "12_12") (pintype "input"))
    )
    (net (code "105") (name "unconnected-(J15-Pad13)") (class "Default")
      (node (ref "J15") (pin "13") (pinfunction "13_13") (pintype "input"))
    )
    (net (code "106") (name "unconnected-(J15-Pad14)") (class "Default")
      (node (ref "J15") (pin "14") (pinfunction "14_14") (pintype "input"))
    )
    (net (code "107") (name "unconnected-(J15-Pad15)") (class "Default")
      (node (ref "J15") (pin "15") (pinfunction "15_15") (pintype "input"))
    )
    (net (code "108") (name "unconnected-(J15-Pad16)") (class "Default")
      (node (ref "J15") (pin "16") (pinfunction "16_16") (pintype "input"))
    )
    (net (code "109") (name "unconnected-(J15-Pad17)") (class "Default")
      (node (ref "J15") (pin "17") (pinfunction "17_17") (pintype "input"))
    )
    (net (code "110") (name "unconnected-(J15-Pad18)") (class "Default")
      (node (ref "J15") (pin "18") (pinfunction "18_18") (pintype "input"))
    )
    (net (code "111") (name "unconnected-(J15-Pad19)") (class "Default")
      (node (ref "J15") (pin "19") (pinfunction "19_19") (pintype "input"))
    )
    (net (code "112") (name "unconnected-(J15-Pad20)") (class "Default")
      (node (ref "J15") (pin "20") (pinfunction "20_20") (pintype "input"))
    )
    (net (code "113") (name "unconnected-(J15-Pad21)") (class "Default")
      (node (ref "J15") (pin "21") (pinfunction "21_21") (pintype "input"))
    )
    (net (code "114") (name "unconnected-(J15-Pad22)") (class "Default")
      (node (ref "J15") (pin "22") (pinfunction "22_22") (pintype "input"))
    )
    (net (code "115") (name "unconnected-(J15-Pad23)") (class "Default")
      (node (ref "J15") (pin "23") (pinfunction "23_23") (pintype "input"))
    )
    (net (code "116") (name "unconnected-(J15-Pad24)") (class "Default")
      (node (ref "J15") (pin "24") (pinfunction "24_24") (pintype "input"))
    )
    (net (code "117") (name "unconnected-(J15-Pad25)") (class "Default")
      (node (ref "J15") (pin "25") (pinfunction "25_25") (pintype "input"))
    )
    (net (code "118") (name "unconnected-(J15-Pad26)") (class "Default")
      (node (ref "J15") (pin "26") (pinfunction "26_26") (pintype "input"))
    )
    (net (code "119") (name "unconnected-(J15-Pad27)") (class "Default")
      (node (ref "J15") (pin "27") (pinfunction "27_27") (pintype "input"))
    )
    (net (code "120") (name "unconnected-(J15-Pad28)") (class "Default")
      (node (ref "J15") (pin "28") (pinfunction "28_28") (pintype "input"))
    )
    (net (code "121") (name "unconnected-(J15-Pad29)") (class "Default")
      (node (ref "J15") (pin "29") (pinfunction "29_29") (pintype "input"))
    )
    (net (code "122") (name "unconnected-(J15-Pad30)") (class "Default")
      (node (ref "J15") (pin "30") (pinfunction "30_30") (pintype "input"))
    )
    (net (code "123") (name "unconnected-(J15-Pad31)") (class "Default")
      (node (ref "J15") (pin "31") (pinfunction "31_31") (pintype "input"))
    )
    (net (code "124") (name "unconnected-(J15-Pad32)") (class "Default")
      (node (ref "J15") (pin "32") (pinfunction "32_32") (pintype "input"))
    )
    (net (code "125") (name "unconnected-(J15-Pad33)") (class "Default")
      (node (ref "J15") (pin "33") (pinfunction "33_33") (pintype "input"))
    )
    (net (code "126") (name "unconnected-(J15-Pad34)") (class "Default")
      (node (ref "J15") (pin "34") (pinfunction "34_34") (pintype "input"))
    )
    (net (code "127") (name "unconnected-(J15-Pad35)") (class "Default")
      (node (ref "J15") (pin "35") (pinfunction "35_35") (pintype "input"))
    )
    (net (code "128") (name "unconnected-(J15-Pad36)") (class "Default")
      (node (ref "J15") (pin "36") (pinfunction "36_36") (pintype "input"))
    )
    (net (code "129") (name "unconnected-(J15-Pad37)") (class "Default")
      (node (ref "J15") (pin "37") (pinfunction "37_37") (pintype "input"))
    )
    (net (code "130") (name "unconnected-(J15-Pad38)") (class "Default")
      (node (ref "J15") (pin "38") (pinfunction "38_38") (pintype "input"))
    )
    (net (code "131") (name "unconnected-(J15-Pad39)") (class "Default")
      (node (ref "J15") (pin "39") (pinfunction "39_39") (pintype "input"))
    )
    (net (code "132") (name "unconnected-(J15-Pad40)") (class "Default")
      (node (ref "J15") (pin "40") (pinfunction "40_40") (pintype "input"))
    )
    (net (code "133") (name "unconnected-(U1-3.3V-Pad17)") (class "Default")
      (node (ref "U1") (pin "17") (pinfunction "3.3V_17") (pintype "unspecified+no_connect"))
    )
    (net (code "134") (name "unconnected-(U1-D5-Pad29)") (class "Default")
      (node (ref "U1") (pin "29") (pinfunction "D5_29") (pintype "unspecified+no_connect"))
    )
    (net (code "135") (name "unconnected-(U1-D6-Pad31)") (class "Default")
      (node (ref "U1") (pin "31") (pinfunction "D6_31") (pintype "unspecified+no_connect"))
    )
    (net (code "136") (name "unconnected-(U1-D7{slash}SPI_CE1_N-Pad26)") (class "Default")
      (node (ref "U1") (pin "26") (pinfunction "D7/SPI_CE1_N_26") (pintype "unspecified+no_connect"))
    )
    (net (code "137") (name "unconnected-(U1-D9{slash}SPI_CIPO-Pad21)") (class "Default")
      (node (ref "U1") (pin "21") (pinfunction "D9/SPI_CIPO_21") (pintype "unspecified+no_connect"))
    )
    (net (code "138") (name "unconnected-(U1-D13-Pad33)") (class "Default")
      (node (ref "U1") (pin "33") (pinfunction "D13_33") (pintype "unspecified+no_connect"))
    )
    (net (code "139") (name "unconnected-(U1-D14{slash}TXD-Pad8)") (class "Default")
      (node (ref "U1") (pin "8") (pinfunction "D14/TXD_8") (pintype "unspecified+no_connect"))
    )
    (net (code "140") (name "unconnected-(U1-D15{slash}RXD-Pad10)") (class "Default")
      (node (ref "U1") (pin "10") (pinfunction "D15/RXD_10") (pintype "unspecified+no_connect"))
    )
    (net (code "141") (name "unconnected-(U1-D16-Pad36)") (class "Default")
      (node (ref "U1") (pin "36") (pinfunction "D16_36") (pintype "unspecified+no_connect"))
    )
    (net (code "142") (name "unconnected-(U1-D19-Pad35)") (class "Default")
      (node (ref "U1") (pin "35") (pinfunction "D19_35") (pintype "unspecified+no_connect"))
    )
    (net (code "143") (name "unconnected-(U1-D20-Pad38)") (class "Default")
      (node (ref "U1") (pin "38") (pinfunction "D20_38") (pintype "unspecified+no_connect"))
    )
    (net (code "144") (name "unconnected-(U1-D22-Pad15)") (class "Default")
      (node (ref "U1") (pin "15") (pinfunction "D22_15") (pintype "unspecified+no_connect"))
    )
    (net (code "145") (name "unconnected-(U1-D23-Pad16)") (class "Default")
      (node (ref "U1") (pin "16") (pinfunction "D23_16") (pintype "unspecified+no_connect"))
    )
    (net (code "146") (name "unconnected-(U1-D24-Pad18)") (class "Default")
      (node (ref "U1") (pin "18") (pinfunction "D24_18") (pintype "unspecified+no_connect"))
    )
    (net (code "147") (name "unconnected-(U1-D26-Pad37)") (class "Default")
      (node (ref "U1") (pin "37") (pinfunction "D26_37") (pintype "unspecified+no_connect"))
    )
    (net (code "148") (name "unconnected-(U1-ID_SC-Pad28)") (class "Default")
      (node (ref "U1") (pin "28") (pinfunction "ID_SC_28") (pintype "unspecified+no_connect"))
    )
    (net (code "149") (name "unconnected-(U1-ID_SD-Pad27)") (class "Default")
      (node (ref "U1") (pin "27") (pinfunction "ID_SD_27") (pintype "unspecified+no_connect"))
    )
    (net (code "150") (name "unconnected-(U2-CSB-Pad5)") (class "Default")
      (node (ref "U2") (pin "5") (pinfunction "CSB_5") (pintype "unspecified+no_connect"))
    )
    (net (code "151") (name "unconnected-(U2-SDO-Pad6)") (class "Default")
      (node (ref "U2") (pin "6") (pinfunction "SDO_6") (pintype "unspecified+no_connect"))
    )
    (net (code "152") (name "unconnected-(U4-NC-Pad2)") (class "Default")
      (node (ref "U4") (pin "2") (pinfunction "NC_2") (pintype "unspecified+no_connect"))
    )
    (net (code "153") (name "unconnected-(U5-INT-Pad5)") (class "Default")
      (node (ref "U5") (pin "5") (pinfunction "INT_5") (pintype "input+no_connect"))
    )
    (net (code "154") (name "unconnected-(U5-M_N-Pad7)") (class "Default")
      (node (ref "U5") (pin "7") (pinfunction "M_N_7") (pintype "input"))
    )
    (net (code "155") (name "unconnected-(U5-M_P-Pad6)") (class "Default")
      (node (ref "U5") (pin "6") (pinfunction "M_P_6") (pintype "input"))
    )
    (net (code "156") (name "unconnected-(U6-OUT-Pad3)") (class "Default")
      (node (ref "U6") (pin "3") (pinfunction "OUT_3") (pintype "unspecified+no_connect"))
    )
    (net (code "157") (name "unconnected-(U6-PUSH-Pad5)") (class "Default")
      (node (ref "U6") (pin "5") (pinfunction "PUSH_5") (pintype "unspecified+no_connect"))
    )
  )
)
